# CODEC.net
KiCad netlist of a schematic drawn in Altium Designer
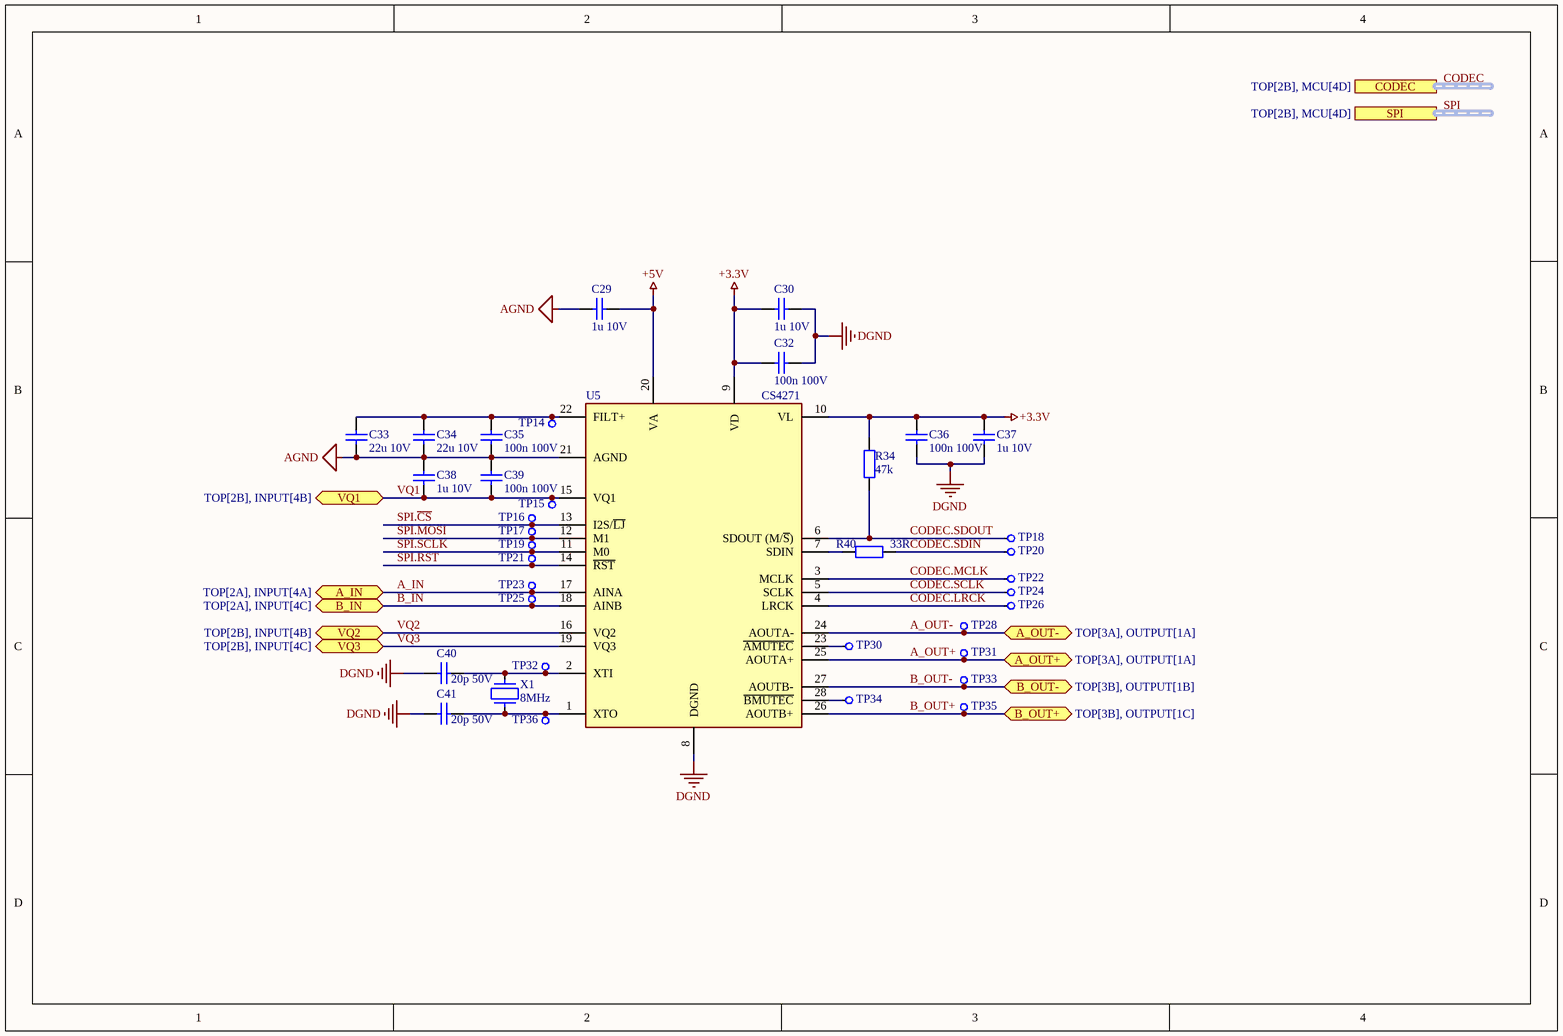
[diagram p0: CODEC.SchDoc]

(export (version "E")
  (design (tool "Eeschema 10.0.6"))
  (components
    (comp (ref "C29")
      (value "1u 10V")
      (footprint "FOOTPRINTS:CAPACITOR 0805")
      (description "Capacitor: ceramic; MLCC; 1uF; 10V; X7R; ±10%; SMD; 0805")
      (fields
        (field (name "MANUFACTURER") "YAGEO")
        (field (name "MANUFACTURER PART NUMBER") "CC0805KKX7R6BB105")
      )
      (libsource (lib "SYMBOLS") (part "Capacitor 1u 10V 10% X7R 0805"))
    )
    (comp (ref "C30")
      (value "1u 10V")
      (footprint "FOOTPRINTS:CAPACITOR 0805")
      (description "Capacitor: ceramic; MLCC; 1uF; 10V; X7R; ±10%; SMD; 0805")
      (fields
        (field (name "MANUFACTURER") "YAGEO")
        (field (name "MANUFACTURER PART NUMBER") "CC0805KKX7R6BB105")
      )
      (libsource (lib "SYMBOLS") (part "Capacitor 1u 10V 10% X7R 0805"))
    )
    (comp (ref "C32")
      (value "100n 100V")
      (footprint "FOOTPRINTS:CAPACITOR 0805")
      (description "Capacitor: ceramic; MLCC; 100nF; 100V; X7R; ±10%; SMD; 0805")
      (fields
        (field (name "MANUFACTURER") "YAGEO")
        (field (name "MANUFACTURER PART NUMBER") "CC0805KKX7R0BB104")
      )
      (libsource (lib "SYMBOLS") (part "Capacitor 100n 100V 10% X7R 0805"))
    )
    (comp (ref "C33")
      (value "22u 10V")
      (footprint "FOOTPRINTS:CAPACITOR 0805")
      (description "Capacitor: ceramic; 22uF; 10V; X5R; ±20%; SMD; 0805")
      (fields
        (field (name "MANUFACTURER") "SAMSUNG")
        (field (name "MANUFACTURER PART NUMBER") "CL21A226MPQNNNE")
      )
      (libsource (lib "SYMBOLS") (part "Capacitor 22u 10V 20% X5R 0805"))
    )
    (comp (ref "C34")
      (value "22u 10V")
      (footprint "FOOTPRINTS:CAPACITOR 0805")
      (description "Capacitor: ceramic; 22uF; 10V; X5R; ±20%; SMD; 0805")
      (fields
        (field (name "MANUFACTURER") "SAMSUNG")
        (field (name "MANUFACTURER PART NUMBER") "CL21A226MPQNNNE")
      )
      (libsource (lib "SYMBOLS") (part "Capacitor 22u 10V 20% X5R 0805"))
    )
    (comp (ref "C35")
      (value "100n 100V")
      (footprint "FOOTPRINTS:CAPACITOR 0805")
      (description "Capacitor: ceramic; MLCC; 100nF; 100V; X7R; ±10%; SMD; 0805")
      (fields
        (field (name "MANUFACTURER") "YAGEO")
        (field (name "MANUFACTURER PART NUMBER") "CC0805KKX7R0BB104")
      )
      (libsource (lib "SYMBOLS") (part "Capacitor 100n 100V 10% X7R 0805"))
    )
    (comp (ref "C36")
      (value "100n 100V")
      (footprint "FOOTPRINTS:CAPACITOR 0805")
      (description "Capacitor: ceramic; MLCC; 100nF; 100V; X7R; ±10%; SMD; 0805")
      (fields
        (field (name "MANUFACTURER") "YAGEO")
        (field (name "MANUFACTURER PART NUMBER") "CC0805KKX7R0BB104")
      )
      (libsource (lib "SYMBOLS") (part "Capacitor 100n 100V 10% X7R 0805"))
    )
    (comp (ref "C37")
      (value "1u 10V")
      (footprint "FOOTPRINTS:CAPACITOR 0805")
      (description "Capacitor: ceramic; MLCC; 1uF; 10V; X7R; ±10%; SMD; 0805")
      (fields
        (field (name "MANUFACTURER") "YAGEO")
        (field (name "MANUFACTURER PART NUMBER") "CC0805KKX7R6BB105")
      )
      (libsource (lib "SYMBOLS") (part "Capacitor 1u 10V 10% X7R 0805"))
    )
    (comp (ref "C38")
      (value "1u 10V")
      (footprint "FOOTPRINTS:CAPACITOR 0805")
      (description "Capacitor: ceramic; MLCC; 1uF; 10V; X7R; ±10%; SMD; 0805")
      (fields
        (field (name "MANUFACTURER") "YAGEO")
        (field (name "MANUFACTURER PART NUMBER") "CC0805KKX7R6BB105")
      )
      (libsource (lib "SYMBOLS") (part "Capacitor 1u 10V 10% X7R 0805"))
    )
    (comp (ref "C39")
      (value "100n 100V")
      (footprint "FOOTPRINTS:CAPACITOR 0805")
      (description "Capacitor: ceramic; MLCC; 100nF; 100V; X7R; ±10%; SMD; 0805")
      (fields
        (field (name "MANUFACTURER") "YAGEO")
        (field (name "MANUFACTURER PART NUMBER") "CC0805KKX7R0BB104")
      )
      (libsource (lib "SYMBOLS") (part "Capacitor 100n 100V 10% X7R 0805"))
    )
    (comp (ref "C40")
      (value "20p 50V")
      (footprint "FOOTPRINTS:CAPACITOR 0805")
      (description "Capacitor: ceramic; MLCC; 20pF; 50V; C0G (NP0); ±5%; SMD; 0805")
      (fields
        (field (name "MANUFACTURER") "KYOCERA AVX")
        (field (name "MANUFACTURER PART NUMBER") "08055A200JAT2A")
      )
      (libsource (lib "SYMBOLS") (part "Capacitor 20p 50V ±5% NP0 0805"))
    )
    (comp (ref "C41")
      (value "20p 50V")
      (footprint "FOOTPRINTS:CAPACITOR 0805")
      (description "Capacitor: ceramic; MLCC; 20pF; 50V; C0G (NP0); ±5%; SMD; 0805")
      (fields
        (field (name "MANUFACTURER") "KYOCERA AVX")
        (field (name "MANUFACTURER PART NUMBER") "08055A200JAT2A")
      )
      (libsource (lib "SYMBOLS") (part "Capacitor 20p 50V ±5% NP0 0805"))
    )
    (comp (ref "R34")
      (value "47k")
      (footprint "FOOTPRINTS:RESISTOR 0805")
      (description "Resistor: thick film; SMD; 0805; 47kΩ; 0.125W; ±1%; -55÷155°C")
      (fields
        (field (name "MANUFACTURER") "Yageo")
        (field (name "MANUFACTURER PART NUMBER") "RC0805FR-0747K")
      )
      (libsource (lib "SYMBOLS") (part "Resistor 47k 1% 1/8W 0805"))
    )
    (comp (ref "R40")
      (value "33R")
      (footprint "FOOTPRINTS:RESISTOR 0805")
      (description "Resistor: thick film; SMD; 0805; 33Ω; 0.125W; ±1%; -55÷155°C")
      (fields
        (field (name "MANUFACTURER") "Yageo")
        (field (name "MANUFACTURER PART NUMBER") "RC0805FR-0733R")
      )
      (libsource (lib "SYMBOLS") (part "Resistor 33R 1% 1/8W 0805"))
    )
    (comp (ref "TP14")
      (value "1mm")
      (footprint "FOOTPRINTS:TEST POINT 1MM")
      (description "Tesp Point 1mm")
      (libsource (lib "SYMBOLS") (part "Mechanical Test Point 1mm"))
    )
    (comp (ref "TP15")
      (value "1mm")
      (footprint "FOOTPRINTS:TEST POINT 1MM")
      (description "Tesp Point 1mm")
      (libsource (lib "SYMBOLS") (part "Mechanical Test Point 1mm"))
    )
    (comp (ref "TP16")
      (value "1mm")
      (footprint "FOOTPRINTS:TEST POINT 1MM")
      (description "Tesp Point 1mm")
      (libsource (lib "SYMBOLS") (part "Mechanical Test Point 1mm"))
    )
    (comp (ref "TP17")
      (value "1mm")
      (footprint "FOOTPRINTS:TEST POINT 1MM")
      (description "Tesp Point 1mm")
      (libsource (lib "SYMBOLS") (part "Mechanical Test Point 1mm"))
    )
    (comp (ref "TP18")
      (value "1mm")
      (footprint "FOOTPRINTS:TEST POINT 1MM")
      (description "Tesp Point 1mm")
      (libsource (lib "SYMBOLS") (part "Mechanical Test Point 1mm"))
    )
    (comp (ref "TP19")
      (value "1mm")
      (footprint "FOOTPRINTS:TEST POINT 1MM")
      (description "Tesp Point 1mm")
      (libsource (lib "SYMBOLS") (part "Mechanical Test Point 1mm"))
    )
    (comp (ref "TP20")
      (value "1mm")
      (footprint "FOOTPRINTS:TEST POINT 1MM")
      (description "Tesp Point 1mm")
      (libsource (lib "SYMBOLS") (part "Mechanical Test Point 1mm"))
    )
    (comp (ref "TP21")
      (value "1mm")
      (footprint "FOOTPRINTS:TEST POINT 1MM")
      (description "Tesp Point 1mm")
      (libsource (lib "SYMBOLS") (part "Mechanical Test Point 1mm"))
    )
    (comp (ref "TP22")
      (value "1mm")
      (footprint "FOOTPRINTS:TEST POINT 1MM")
      (description "Tesp Point 1mm")
      (libsource (lib "SYMBOLS") (part "Mechanical Test Point 1mm"))
    )
    (comp (ref "TP23")
      (value "1mm")
      (footprint "FOOTPRINTS:TEST POINT 1MM")
      (description "Tesp Point 1mm")
      (libsource (lib "SYMBOLS") (part "Mechanical Test Point 1mm"))
    )
    (comp (ref "TP24")
      (value "1mm")
      (footprint "FOOTPRINTS:TEST POINT 1MM")
      (description "Tesp Point 1mm")
      (libsource (lib "SYMBOLS") (part "Mechanical Test Point 1mm"))
    )
    (comp (ref "TP25")
      (value "1mm")
      (footprint "FOOTPRINTS:TEST POINT 1MM")
      (description "Tesp Point 1mm")
      (libsource (lib "SYMBOLS") (part "Mechanical Test Point 1mm"))
    )
    (comp (ref "TP26")
      (value "1mm")
      (footprint "FOOTPRINTS:TEST POINT 1MM")
      (description "Tesp Point 1mm")
      (libsource (lib "SYMBOLS") (part "Mechanical Test Point 1mm"))
    )
    (comp (ref "TP28")
      (value "1mm")
      (footprint "FOOTPRINTS:TEST POINT 1MM")
      (description "Tesp Point 1mm")
      (libsource (lib "SYMBOLS") (part "Mechanical Test Point 1mm"))
    )
    (comp (ref "TP30")
      (value "1mm")
      (footprint "FOOTPRINTS:TEST POINT 1MM")
      (description "Tesp Point 1mm")
      (libsource (lib "SYMBOLS") (part "Mechanical Test Point 1mm"))
    )
    (comp (ref "TP31")
      (value "1mm")
      (footprint "FOOTPRINTS:TEST POINT 1MM")
      (description "Tesp Point 1mm")
      (libsource (lib "SYMBOLS") (part "Mechanical Test Point 1mm"))
    )
    (comp (ref "TP32")
      (value "1mm")
      (footprint "FOOTPRINTS:TEST POINT 1MM")
      (description "Tesp Point 1mm")
      (libsource (lib "SYMBOLS") (part "Mechanical Test Point 1mm"))
    )
    (comp (ref "TP33")
      (value "1mm")
      (footprint "FOOTPRINTS:TEST POINT 1MM")
      (description "Tesp Point 1mm")
      (libsource (lib "SYMBOLS") (part "Mechanical Test Point 1mm"))
    )
    (comp (ref "TP34")
      (value "1mm")
      (footprint "FOOTPRINTS:TEST POINT 1MM")
      (description "Tesp Point 1mm")
      (libsource (lib "SYMBOLS") (part "Mechanical Test Point 1mm"))
    )
    (comp (ref "TP35")
      (value "1mm")
      (footprint "FOOTPRINTS:TEST POINT 1MM")
      (description "Tesp Point 1mm")
      (libsource (lib "SYMBOLS") (part "Mechanical Test Point 1mm"))
    )
    (comp (ref "TP36")
      (value "1mm")
      (footprint "FOOTPRINTS:TEST POINT 1MM")
      (description "Tesp Point 1mm")
      (libsource (lib "SYMBOLS") (part "Mechanical Test Point 1mm"))
    )
    (comp (ref "U5")
      (value "CS4271")
      (footprint "FOOTPRINTS:TSSOP-28")
      (description "Interface - CODECs Stereo Audio CODEC 108 dB 192 kHz")
      (fields
        (field (name "MANUFACTURER PART NUMBER") "CS4271-CZZ")
        (field (name "MANUFACTURER") "Cirrus Logic")
      )
      (libsource (lib "SYMBOLS") (part "IC Audio CODEC CS4271 TSSOP-28"))
    )
    (comp (ref "X1")
      (value "8MHz")
      (footprint "FOOTPRINTS:OSCILLATOR 8MHZ SMD")
      (description "Crystals CRYSTAL 8.0000MHZ 20PF SMD")
      (fields
        (field (name "MANUFACTURER") "ABRACON")
        (field (name "MANUFACTURER PART NUMBER") "ABLS-8.000MHZ-20-B-3-H-T")
      )
      (libsource (lib "SYMBOLS") (part "Crystal 8MHz 20p SMD"))
    )
  )
  (nets
    (net (code "3") (name "+3.3V") (class "Default")
      (node (ref "C30") (pin "1") (pinfunction "1_1") (pintype "passive"))
      (node (ref "C32") (pin "1") (pinfunction "1_1") (pintype "passive"))
      (node (ref "C36") (pin "2") (pinfunction "2_2") (pintype "passive"))
      (node (ref "C37") (pin "2") (pinfunction "2_2") (pintype "passive"))
      (node (ref "R34") (pin "2") (pinfunction "2_2") (pintype "passive"))
      (node (ref "U5") (pin "10") (pinfunction "VL_10") (pintype "passive"))
      (node (ref "U5") (pin "9") (pinfunction "VD_9") (pintype "passive"))
    )
    (net (code "4") (name "+5V") (class "Default")
      (node (ref "C29") (pin "1") (pinfunction "1_1") (pintype "passive"))
      (node (ref "U5") (pin "20") (pinfunction "VA_20") (pintype "passive"))
    )
    (net (code "5") (name "/A_IN") (class "Default")
      (node (ref "TP23") (pin "1") (pinfunction "1_1") (pintype "passive"))
      (node (ref "U5") (pin "17") (pinfunction "AINA_17") (pintype "passive"))
    )
    (net (code "6") (name "/A_OUT+") (class "Default")
      (node (ref "TP31") (pin "1") (pinfunction "1_1") (pintype "passive"))
      (node (ref "U5") (pin "25") (pinfunction "AOUTA+_25") (pintype "passive"))
    )
    (net (code "7") (name "/A_OUT-") (class "Default")
      (node (ref "TP28") (pin "1") (pinfunction "1_1") (pintype "passive"))
      (node (ref "U5") (pin "24") (pinfunction "AOUTA-_24") (pintype "passive"))
    )
    (net (code "8") (name "/B_IN") (class "Default")
      (node (ref "TP25") (pin "1") (pinfunction "1_1") (pintype "passive"))
      (node (ref "U5") (pin "18") (pinfunction "AINB_18") (pintype "passive"))
    )
    (net (code "9") (name "/B_OUT+") (class "Default")
      (node (ref "TP35") (pin "1") (pinfunction "1_1") (pintype "passive"))
      (node (ref "U5") (pin "26") (pinfunction "AOUTB+_26") (pintype "passive"))
    )
    (net (code "10") (name "/B_OUT-") (class "Default")
      (node (ref "TP33") (pin "1") (pinfunction "1_1") (pintype "passive"))
      (node (ref "U5") (pin "27") (pinfunction "AOUTB-_27") (pintype "passive"))
    )
    (net (code "11") (name "/CODEC.LRCK") (class "Default")
      (node (ref "TP26") (pin "1") (pinfunction "1_1") (pintype "passive"))
      (node (ref "U5") (pin "4") (pinfunction "LRCK_4") (pintype "passive"))
    )
    (net (code "12") (name "/CODEC.MCLK") (class "Default")
      (node (ref "TP22") (pin "1") (pinfunction "1_1") (pintype "passive"))
      (node (ref "U5") (pin "3") (pinfunction "MCLK_3") (pintype "passive"))
    )
    (net (code "13") (name "/CODEC.SCLK") (class "Default")
      (node (ref "TP24") (pin "1") (pinfunction "1_1") (pintype "passive"))
      (node (ref "U5") (pin "5") (pinfunction "SCLK_5") (pintype "passive"))
    )
    (net (code "14") (name "/CODEC.SDIN") (class "Default")
      (node (ref "R40") (pin "2") (pinfunction "2_2") (pintype "passive"))
      (node (ref "TP20") (pin "1") (pinfunction "1_1") (pintype "passive"))
    )
    (net (code "15") (name "/CODEC.SDOUT") (class "Default")
      (node (ref "R34") (pin "1") (pinfunction "1_1") (pintype "passive"))
      (node (ref "TP18") (pin "1") (pinfunction "1_1") (pintype "passive"))
      (node (ref "U5") (pin "6") (pinfunction "SDOUT_(M/~{S})_6") (pintype "passive"))
    )
    (net (code "16") (name "/SPI.MOSI") (class "Default")
      (node (ref "TP17") (pin "1") (pinfunction "1_1") (pintype "passive"))
      (node (ref "U5") (pin "12") (pinfunction "M1_12") (pintype "passive"))
    )
    (net (code "17") (name "/SPI.SCLK") (class "Default")
      (node (ref "TP19") (pin "1") (pinfunction "1_1") (pintype "passive"))
      (node (ref "U5") (pin "11") (pinfunction "M0_11") (pintype "passive"))
    )
    (net (code "18") (name "/SPI.~{CS}") (class "Default")
      (node (ref "TP16") (pin "1") (pinfunction "1_1") (pintype "passive"))
      (node (ref "U5") (pin "13") (pinfunction "I2S/~{LJ}_13") (pintype "passive"))
    )
    (net (code "19") (name "/SPI.~{RST}") (class "Default")
      (node (ref "TP21") (pin "1") (pinfunction "1_1") (pintype "passive"))
      (node (ref "U5") (pin "14") (pinfunction "~{RST}_14") (pintype "passive"))
    )
    (net (code "20") (name "/VQ1") (class "Default")
      (node (ref "C38") (pin "1") (pinfunction "1_1") (pintype "passive"))
      (node (ref "C39") (pin "1") (pinfunction "1_1") (pintype "passive"))
      (node (ref "TP15") (pin "1") (pinfunction "1_1") (pintype "passive"))
      (node (ref "U5") (pin "15") (pinfunction "VQ1_15") (pintype "passive"))
    )
    (net (code "21") (name "/VQ2") (class "Default")
      (node (ref "U5") (pin "16") (pinfunction "VQ2_16") (pintype "passive"))
    )
    (net (code "22") (name "/VQ3") (class "Default")
      (node (ref "U5") (pin "19") (pinfunction "VQ3_19") (pintype "passive"))
    )
    (net (code "25") (name "AGND") (class "Default")
      (node (ref "C29") (pin "2") (pinfunction "2_2") (pintype "passive"))
      (node (ref "C33") (pin "1") (pinfunction "1_1") (pintype "passive"))
      (node (ref "C34") (pin "1") (pinfunction "1_1") (pintype "passive"))
      (node (ref "C35") (pin "1") (pinfunction "1_1") (pintype "passive"))
      (node (ref "C38") (pin "2") (pinfunction "2_2") (pintype "passive"))
      (node (ref "C39") (pin "2") (pinfunction "2_2") (pintype "passive"))
      (node (ref "U5") (pin "21") (pinfunction "AGND_21") (pintype "passive"))
    )
    (net (code "26") (name "DGND") (class "Default")
      (node (ref "C30") (pin "2") (pinfunction "2_2") (pintype "passive"))
      (node (ref "C32") (pin "2") (pinfunction "2_2") (pintype "passive"))
      (node (ref "C36") (pin "1") (pinfunction "1_1") (pintype "passive"))
      (node (ref "C37") (pin "1") (pinfunction "1_1") (pintype "passive"))
      (node (ref "C40") (pin "2") (pinfunction "2_2") (pintype "passive"))
      (node (ref "C41") (pin "2") (pinfunction "2_2") (pintype "passive"))
      (node (ref "U5") (pin "8") (pinfunction "DGND_8") (pintype "passive"))
    )
    (net (code "27") (name "Net-(U5-FILT+)") (class "Default")
      (node (ref "C33") (pin "2") (pinfunction "2_2") (pintype "passive"))
      (node (ref "C34") (pin "2") (pinfunction "2_2") (pintype "passive"))
      (node (ref "C35") (pin "2") (pinfunction "2_2") (pintype "passive"))
      (node (ref "TP14") (pin "1") (pinfunction "1_1") (pintype "passive"))
      (node (ref "U5") (pin "22") (pinfunction "FILT+_22") (pintype "passive"))
    )
    (net (code "28") (name "Net-(U5-SDIN)") (class "Default")
      (node (ref "R40") (pin "1") (pinfunction "1_1") (pintype "passive"))
      (node (ref "U5") (pin "7") (pinfunction "SDIN_7") (pintype "passive"))
    )
    (net (code "29") (name "Net-(U5-XTI)") (class "Default")
      (node (ref "C40") (pin "1") (pinfunction "1_1") (pintype "passive"))
      (node (ref "TP32") (pin "1") (pinfunction "1_1") (pintype "passive"))
      (node (ref "U5") (pin "2") (pinfunction "XTI_2") (pintype "passive"))
      (node (ref "X1") (pin "2") (pinfunction "2_2") (pintype "passive"))
    )
    (net (code "30") (name "Net-(U5-XTO)") (class "Default")
      (node (ref "C41") (pin "1") (pinfunction "1_1") (pintype "passive"))
      (node (ref "TP36") (pin "1") (pinfunction "1_1") (pintype "passive"))
      (node (ref "U5") (pin "1") (pinfunction "XTO_1") (pintype "passive"))
      (node (ref "X1") (pin "1") (pinfunction "1_1") (pintype "passive"))
    )
    (net (code "31") (name "Net-(U5-~{AMUTEC})") (class "Default")
      (node (ref "TP30") (pin "1") (pinfunction "1_1") (pintype "passive"))
      (node (ref "U5") (pin "23") (pinfunction "~{AMUTEC}_23") (pintype "passive"))
    )
    (net (code "32") (name "Net-(U5-~{BMUTEC})") (class "Default")
      (node (ref "TP34") (pin "1") (pinfunction "1_1") (pintype "passive"))
      (node (ref "U5") (pin "28") (pinfunction "~{BMUTEC}_28") (pintype "passive"))
    )
  )
)
